# Sheet13.net
KiCad netlist of a schematic drawn in Altium Designer
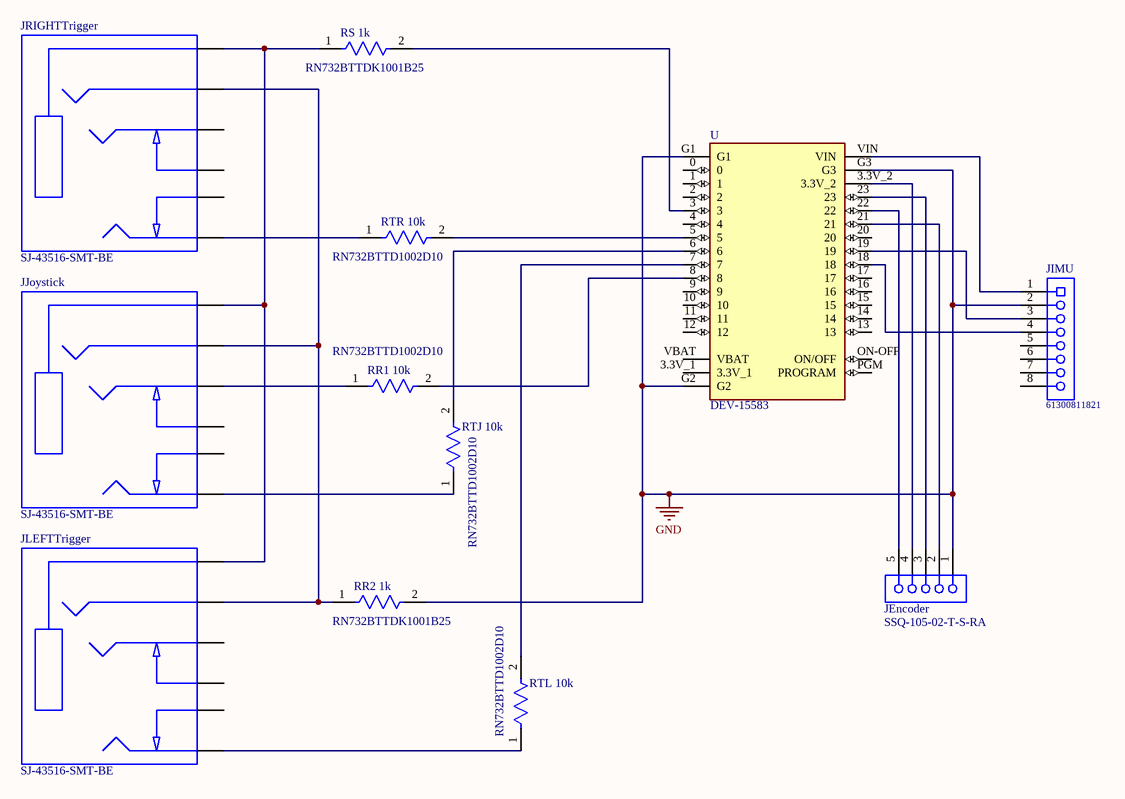
[diagram p0: Sheet13.SchDoc]

(export (version "E")
  (design (tool "Eeschema 10.0.6"))
  (components
    (comp (ref "JEncoder")
      (value "SSQ-105-02-T-S-RA")
      (footprint "SMTC-SSQ-105-02-X-S-RA")
      (description "SQ Post Socket, Through-hole, Right Angle, -55 to 105 degC, 2.54 mm Pitch, 5-Pin, Female, RoHS")
      (fields (field (name "MANUFACTURER") "Samtec"))
      (libsource (lib "Altium Content Vault") (part "SMTC-SSQ-105-02-X-S-RA"))
    )
    (comp (ref "JIMU")
      (value "61300811821")
      (footprint "61300811821")
      (description "THT Vertical Socket Header WR-PHD, Pitch 2.54 mm, Single Row, 8 pins")
      (fields (field (name "MANUFACTURER") "Wurth Elektronik") (field (name "PUBLISHER") "WurthElektronik"))
      (libsource (lib "Altium Content Vault") (part "WE-CN-1P-F-R8"))
    )
    (comp (ref "JJoystick")
      (value "SJ-43516-SMT-BE")
      (footprint "CUI_SJ-43516-SMT-BE")
      (description "3.5 mm, 4 Conductors, Right Angle, Surface Mount _SMT_, Audio Jack Connector")
      (fields (field (name "MP") "SJ-43516-SMT-TR-BE") (field (name "MF") "CUI Devices"))
      (libsource (lib "SJ-43516-SMT-BE") (part "SJ-43516-SMT-BE"))
    )
    (comp (ref "JLEFTTrigger")
      (value "SJ-43516-SMT-BE")
      (footprint "CUI_SJ-43516-SMT-BE")
      (description "3.5 mm, 4 Conductors, Right Angle, Surface Mount _SMT_, Audio Jack Connector")
      (fields (field (name "MP") "SJ-43516-SMT-TR-BE") (field (name "MF") "CUI Devices"))
      (libsource (lib "SJ-43516-SMT-BE") (part "SJ-43516-SMT-BE"))
    )
    (comp (ref "JRIGHTTrigger")
      (value "SJ-43516-SMT-BE")
      (footprint "CUI_SJ-43516-SMT-BE")
      (description "3.5 mm, 4 Conductors, Right Angle, Surface Mount _SMT_, Audio Jack Connector")
      (fields (field (name "MP") "SJ-43516-SMT-TR-BE") (field (name "MF") "CUI Devices"))
      (libsource (lib "SJ-43516-SMT-BE") (part "SJ-43516-SMT-BE"))
    )
    (comp (ref "RR1 10k")
      (value "RN732BTTD1002D10")
      (footprint "FP-RN732B-IPC_B")
      (description "10kΩ ±0.5% 0.125W, 1/8W Chip Resistor 1206 (3216 Metric) Moisture Resistant Thin Film")
      (fields (field (name "TOLERANCE") "0.5%"))
      (libsource (lib "Altium Content Vault") (part "1029c3af85768c4190bb7ad29bc67b5"))
    )
    (comp (ref "RR2 1k")
      (value "RN732BTTDK1001B25")
      (footprint "FP-RN732B-IPC_C")
      (description "1kΩ ±0.1% 0.125W, 1/8W Chip Resistor 1206 (3216 Metric) Moisture Resistant Thin Film")
      (fields (field (name "TOLERANCE") "0.1%"))
      (libsource (lib "Altium Content Vault") (part "1029c3af85768c4190bb7ad29bc67b5"))
    )
    (comp (ref "RS 1k")
      (value "RN732BTTDK1001B25")
      (footprint "FP-RN732B-IPC_C")
      (description "1kΩ ±0.1% 0.125W, 1/8W Chip Resistor 1206 (3216 Metric) Moisture Resistant Thin Film")
      (fields (field (name "TOLERANCE") "0.1%"))
      (libsource (lib "Altium Content Vault") (part "1029c3af85768c4190bb7ad29bc67b5"))
    )
    (comp (ref "RTJ 10k")
      (value "RN732BTTD1002D10")
      (footprint "FP-RN732B-IPC_B")
      (description "10kΩ ±0.5% 0.125W, 1/8W Chip Resistor 1206 (3216 Metric) Moisture Resistant Thin Film")
      (fields (field (name "TOLERANCE") "0.5%"))
      (libsource (lib "Altium Content Vault") (part "1029c3af85768c4190bb7ad29bc67b5"))
    )
    (comp (ref "RTL 10k")
      (value "RN732BTTD1002D10")
      (footprint "FP-RN732B-IPC_B")
      (description "10kΩ ±0.5% 0.125W, 1/8W Chip Resistor 1206 (3216 Metric) Moisture Resistant Thin Film")
      (fields (field (name "TOLERANCE") "0.5%"))
      (libsource (lib "Altium Content Vault") (part "1029c3af85768c4190bb7ad29bc67b5"))
    )
    (comp (ref "RTR 10k")
      (value "RN732BTTD1002D10")
      (footprint "FP-RN732B-IPC_B")
      (description "10kΩ ±0.5% 0.125W, 1/8W Chip Resistor 1206 (3216 Metric) Moisture Resistant Thin Film")
      (fields (field (name "TOLERANCE") "0.5%"))
      (libsource (lib "Altium Content Vault") (part "1029c3af85768c4190bb7ad29bc67b5"))
    )
    (comp (ref "U")
      (value "DEV-15583")
      (footprint "MODULE_DEV-15583")
      (description "RT1062 Teensy 4.0 i.MX ARMÂ® CortexÂ®-M7 MPU Embedded Evaluation Board")
      (fields
        (field (name "MF") "SparkFun Electronics")
        (field (name "DIGI-KEY_PART_NUMBER") "1568-DEV-15583-ND")
      )
      (libsource (lib "DEV-15583") (part "DEV-15583"))
    )
  )
  (nets
    (net (code "1") (name "GND") (class "Default")
      (node (ref "JEncoder") (pin "1") (pinfunction "1_1") (pintype "passive"))
      (node (ref "JIMU") (pin "2") (pinfunction "2_2") (pintype "passive"))
      (node (ref "RR2 1k") (pin "2") (pinfunction "2_2") (pintype "passive"))
      (node (ref "U") (pin "G1") (pinfunction "G1_G1") (pintype "power_in"))
      (node (ref "U") (pin "G2") (pinfunction "G2_G2") (pintype "power_in"))
      (node (ref "U") (pin "G3") (pinfunction "G3_G3") (pintype "power_in"))
    )
    (net (code "2") (name "Net-(JEncoder-Pad2)") (class "Default")
      (node (ref "JEncoder") (pin "2") (pinfunction "2_2") (pintype "passive"))
      (node (ref "U") (pin "21") (pinfunction "21_21") (pintype "bidirectional"))
    )
    (net (code "3") (name "Net-(JEncoder-Pad3)") (class "Default")
      (node (ref "JEncoder") (pin "3") (pinfunction "3_3") (pintype "passive"))
      (node (ref "U") (pin "23") (pinfunction "23_23") (pintype "bidirectional"))
    )
    (net (code "4") (name "Net-(JEncoder-Pad4)") (class "Default")
      (node (ref "JEncoder") (pin "4") (pinfunction "4_4") (pintype "passive"))
      (node (ref "U") (pin "3.3V_2") (pinfunction "3.3V_2_3.3V_2") (pintype "power_in"))
    )
    (net (code "5") (name "Net-(JEncoder-Pad5)") (class "Default")
      (node (ref "JEncoder") (pin "5") (pinfunction "5_5") (pintype "passive"))
      (node (ref "U") (pin "22") (pinfunction "22_22") (pintype "bidirectional"))
    )
    (net (code "6") (name "Net-(JIMU-Pad1)") (class "Default")
      (node (ref "JIMU") (pin "1") (pinfunction "1_1") (pintype "passive"))
      (node (ref "U") (pin "VIN") (pinfunction "VIN_VIN") (pintype "power_in"))
    )
    (net (code "7") (name "Net-(JIMU-Pad3)") (class "Default")
      (node (ref "JIMU") (pin "3") (pinfunction "3_3") (pintype "passive"))
      (node (ref "U") (pin "19") (pinfunction "19_19") (pintype "bidirectional"))
    )
    (net (code "8") (name "Net-(JIMU-Pad4)") (class "Default")
      (node (ref "JIMU") (pin "4") (pinfunction "4_4") (pintype "passive"))
      (node (ref "U") (pin "18") (pinfunction "18_18") (pintype "bidirectional"))
    )
    (net (code "9") (name "Net-(JJoystick-RING1)") (class "Default")
      (node (ref "JJoystick") (pin "3") (pinfunction "RING1_3") (pintype "passive"))
      (node (ref "RR1 10k") (pin "1") (pinfunction "1_1") (pintype "passive"))
    )
    (net (code "10") (name "Net-(JJoystick-RING2)") (class "Default")
      (node (ref "JJoystick") (pin "4") (pinfunction "RING2_4") (pintype "passive"))
      (node (ref "JLEFTTrigger") (pin "4") (pinfunction "RING2_4") (pintype "passive"))
      (node (ref "JRIGHTTrigger") (pin "4") (pinfunction "RING2_4") (pintype "passive"))
      (node (ref "RR2 1k") (pin "1") (pinfunction "1_1") (pintype "passive"))
    )
    (net (code "11") (name "Net-(JJoystick-SLEEVE)") (class "Default")
      (node (ref "JJoystick") (pin "1") (pinfunction "SLEEVE_1") (pintype "passive"))
      (node (ref "JLEFTTrigger") (pin "1") (pinfunction "SLEEVE_1") (pintype "passive"))
      (node (ref "JRIGHTTrigger") (pin "1") (pinfunction "SLEEVE_1") (pintype "passive"))
      (node (ref "RS 1k") (pin "1") (pinfunction "1_1") (pintype "passive"))
    )
    (net (code "12") (name "Net-(JJoystick-TIP)") (class "Default")
      (node (ref "JJoystick") (pin "2") (pinfunction "TIP_2") (pintype "passive"))
      (node (ref "RTJ 10k") (pin "1") (pinfunction "1_1") (pintype "passive"))
    )
    (net (code "13") (name "Net-(JLEFTTrigger-TIP)") (class "Default")
      (node (ref "JLEFTTrigger") (pin "2") (pinfunction "TIP_2") (pintype "passive"))
      (node (ref "RTL 10k") (pin "1") (pinfunction "1_1") (pintype "passive"))
    )
    (net (code "14") (name "Net-(JRIGHTTrigger-TIP)") (class "Default")
      (node (ref "JRIGHTTrigger") (pin "2") (pinfunction "TIP_2") (pintype "passive"))
      (node (ref "RTR 10k") (pin "1") (pinfunction "1_1") (pintype "passive"))
    )
    (net (code "15") (name "Net-(RR1 10k-Pad2)") (class "Default")
      (node (ref "RR1 10k") (pin "2") (pinfunction "2_2") (pintype "passive"))
      (node (ref "U") (pin "8") (pinfunction "8_8") (pintype "bidirectional"))
    )
    (net (code "16") (name "Net-(RS 1k-Pad2)") (class "Default")
      (node (ref "RS 1k") (pin "2") (pinfunction "2_2") (pintype "passive"))
      (node (ref "U") (pin "3") (pinfunction "3_3") (pintype "bidirectional"))
    )
    (net (code "17") (name "Net-(RTJ 10k-Pad2)") (class "Default")
      (node (ref "RTJ 10k") (pin "2") (pinfunction "2_2") (pintype "passive"))
      (node (ref "U") (pin "6") (pinfunction "6_6") (pintype "bidirectional"))
    )
    (net (code "18") (name "Net-(RTL 10k-Pad2)") (class "Default")
      (node (ref "RTL 10k") (pin "2") (pinfunction "2_2") (pintype "passive"))
      (node (ref "U") (pin "7") (pinfunction "7_7") (pintype "bidirectional"))
    )
    (net (code "19") (name "Net-(RTR 10k-Pad2)") (class "Default")
      (node (ref "RTR 10k") (pin "2") (pinfunction "2_2") (pintype "passive"))
      (node (ref "U") (pin "5") (pinfunction "5_5") (pintype "bidirectional"))
    )
    (net (code "20") (name "unconnected-(JIMU-Pad5)") (class "Default")
      (node (ref "JIMU") (pin "5") (pinfunction "5_5") (pintype "passive"))
    )
    (net (code "21") (name "unconnected-(JIMU-Pad6)") (class "Default")
      (node (ref "JIMU") (pin "6") (pinfunction "6_6") (pintype "passive"))
    )
    (net (code "22") (name "unconnected-(JIMU-Pad7)") (class "Default")
      (node (ref "JIMU") (pin "7") (pinfunction "7_7") (pintype "passive"))
    )
    (net (code "23") (name "unconnected-(JIMU-Pad8)") (class "Default")
      (node (ref "JIMU") (pin "8") (pinfunction "8_8") (pintype "passive"))
    )
    (net (code "24") (name "unconnected-(JJoystick-RING_SWITCH-Pad6)") (class "Default")
      (node (ref "JJoystick") (pin "6") (pinfunction "RING_SWITCH_6") (pintype "passive"))
    )
    (net (code "25") (name "unconnected-(JJoystick-TIP_SWITCH-Pad5)") (class "Default")
      (node (ref "JJoystick") (pin "5") (pinfunction "TIP_SWITCH_5") (pintype "passive"))
    )
    (net (code "26") (name "unconnected-(JLEFTTrigger-RING1-Pad3)") (class "Default")
      (node (ref "JLEFTTrigger") (pin "3") (pinfunction "RING1_3") (pintype "passive"))
    )
    (net (code "27") (name "unconnected-(JLEFTTrigger-RING_SWITCH-Pad6)") (class "Default")
      (node (ref "JLEFTTrigger") (pin "6") (pinfunction "RING_SWITCH_6") (pintype "passive"))
    )
    (net (code "28") (name "unconnected-(JLEFTTrigger-TIP_SWITCH-Pad5)") (class "Default")
      (node (ref "JLEFTTrigger") (pin "5") (pinfunction "TIP_SWITCH_5") (pintype "passive"))
    )
    (net (code "29") (name "unconnected-(JRIGHTTrigger-RING1-Pad3)") (class "Default")
      (node (ref "JRIGHTTrigger") (pin "3") (pinfunction "RING1_3") (pintype "passive"))
    )
    (net (code "30") (name "unconnected-(JRIGHTTrigger-RING_SWITCH-Pad6)") (class "Default")
      (node (ref "JRIGHTTrigger") (pin "6") (pinfunction "RING_SWITCH_6") (pintype "passive"))
    )
    (net (code "31") (name "unconnected-(JRIGHTTrigger-TIP_SWITCH-Pad5)") (class "Default")
      (node (ref "JRIGHTTrigger") (pin "5") (pinfunction "TIP_SWITCH_5") (pintype "passive"))
    )
    (net (code "32") (name "unconnected-(U-ON{slash}OFF-PadON-OFF)") (class "Default")
      (node (ref "U") (pin "ON-OFF") (pinfunction "ON/OFF_ON-OFF") (pintype "bidirectional"))
    )
    (net (code "33") (name "unconnected-(U-PROGRAM-PadPGM)") (class "Default")
      (node (ref "U") (pin "PGM") (pinfunction "PROGRAM_PGM") (pintype "bidirectional"))
    )
    (net (code "34") (name "unconnected-(U-Pad0)") (class "Default")
      (node (ref "U") (pin "0") (pinfunction "0_0") (pintype "bidirectional"))
    )
    (net (code "35") (name "unconnected-(U-Pad1)") (class "Default")
      (node (ref "U") (pin "1") (pinfunction "1_1") (pintype "bidirectional"))
    )
    (net (code "36") (name "unconnected-(U-Pad2)") (class "Default")
      (node (ref "U") (pin "2") (pinfunction "2_2") (pintype "bidirectional"))
    )
    (net (code "37") (name "unconnected-(U-Pad3.3V_1)") (class "Default")
      (node (ref "U") (pin "3.3V_1") (pinfunction "3.3V_1_3.3V_1") (pintype "power_in"))
    )
    (net (code "38") (name "unconnected-(U-Pad4)") (class "Default")
      (node (ref "U") (pin "4") (pinfunction "4_4") (pintype "bidirectional"))
    )
    (net (code "39") (name "unconnected-(U-Pad9)") (class "Default")
      (node (ref "U") (pin "9") (pinfunction "9_9") (pintype "bidirectional"))
    )
    (net (code "40") (name "unconnected-(U-Pad10)") (class "Default")
      (node (ref "U") (pin "10") (pinfunction "10_10") (pintype "bidirectional"))
    )
    (net (code "41") (name "unconnected-(U-Pad11)") (class "Default")
      (node (ref "U") (pin "11") (pinfunction "11_11") (pintype "bidirectional"))
    )
    (net (code "42") (name "unconnected-(U-Pad12)") (class "Default")
      (node (ref "U") (pin "12") (pinfunction "12_12") (pintype "bidirectional"))
    )
    (net (code "43") (name "unconnected-(U-Pad13)") (class "Default")
      (node (ref "U") (pin "13") (pinfunction "13_13") (pintype "bidirectional"))
    )
    (net (code "44") (name "unconnected-(U-Pad14)") (class "Default")
      (node (ref "U") (pin "14") (pinfunction "14_14") (pintype "bidirectional"))
    )
    (net (code "45") (name "unconnected-(U-Pad15)") (class "Default")
      (node (ref "U") (pin "15") (pinfunction "15_15") (pintype "bidirectional"))
    )
    (net (code "46") (name "unconnected-(U-Pad16)") (class "Default")
      (node (ref "U") (pin "16") (pinfunction "16_16") (pintype "bidirectional"))
    )
    (net (code "47") (name "unconnected-(U-Pad17)") (class "Default")
      (node (ref "U") (pin "17") (pinfunction "17_17") (pintype "bidirectional"))
    )
    (net (code "48") (name "unconnected-(U-Pad20)") (class "Default")
      (node (ref "U") (pin "20") (pinfunction "20_20") (pintype "bidirectional"))
    )
    (net (code "49") (name "unconnected-(U-PadVBAT)") (class "Default")
      (node (ref "U") (pin "VBAT") (pinfunction "VBAT_VBAT") (pintype "power_in"))
    )
  )
)
